# AK4558EN_PMOD.net
KiCad netlist of a schematic drawn in EAGLE
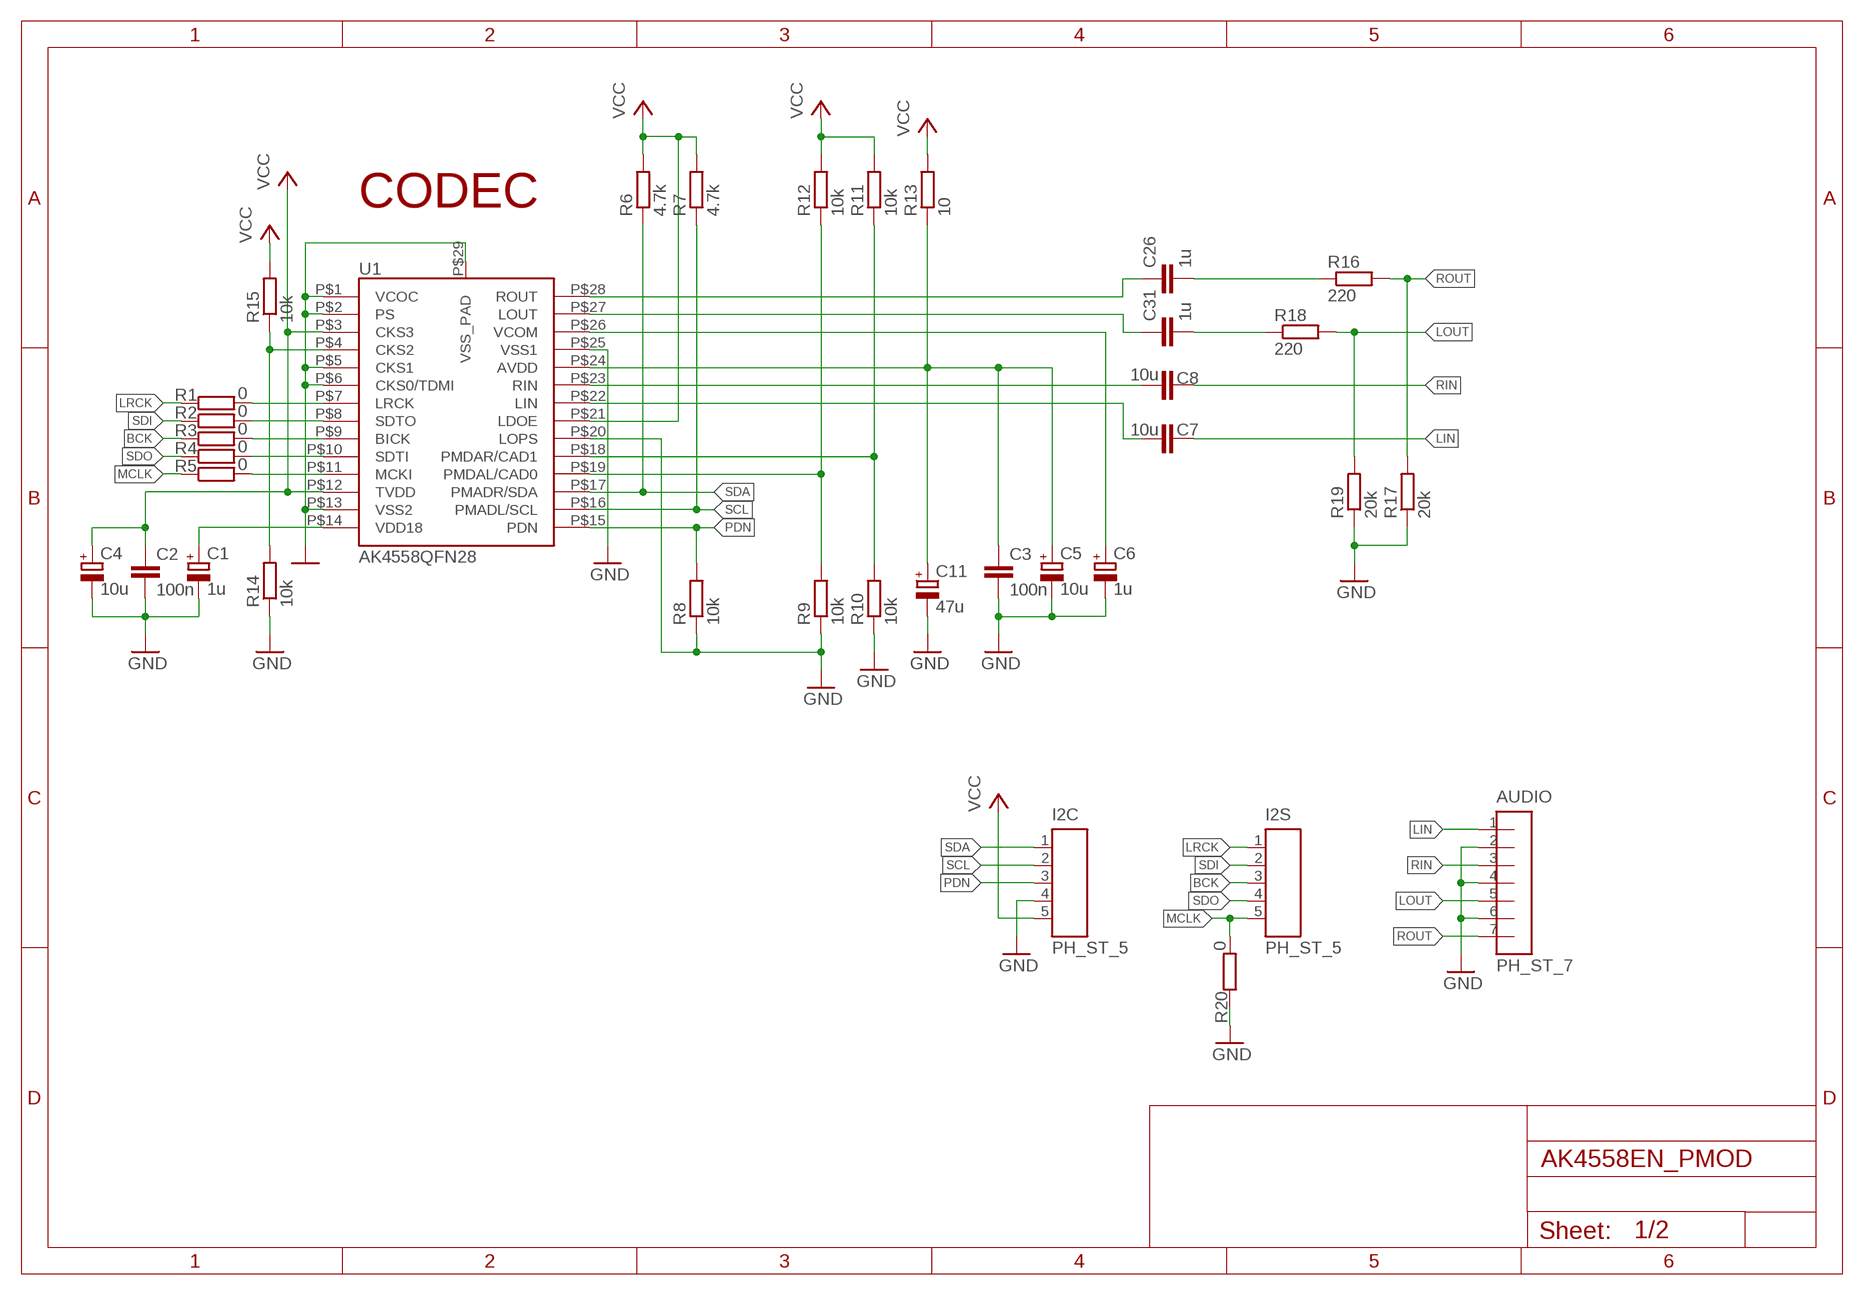
[diagram p0: schematic, sheet 1]
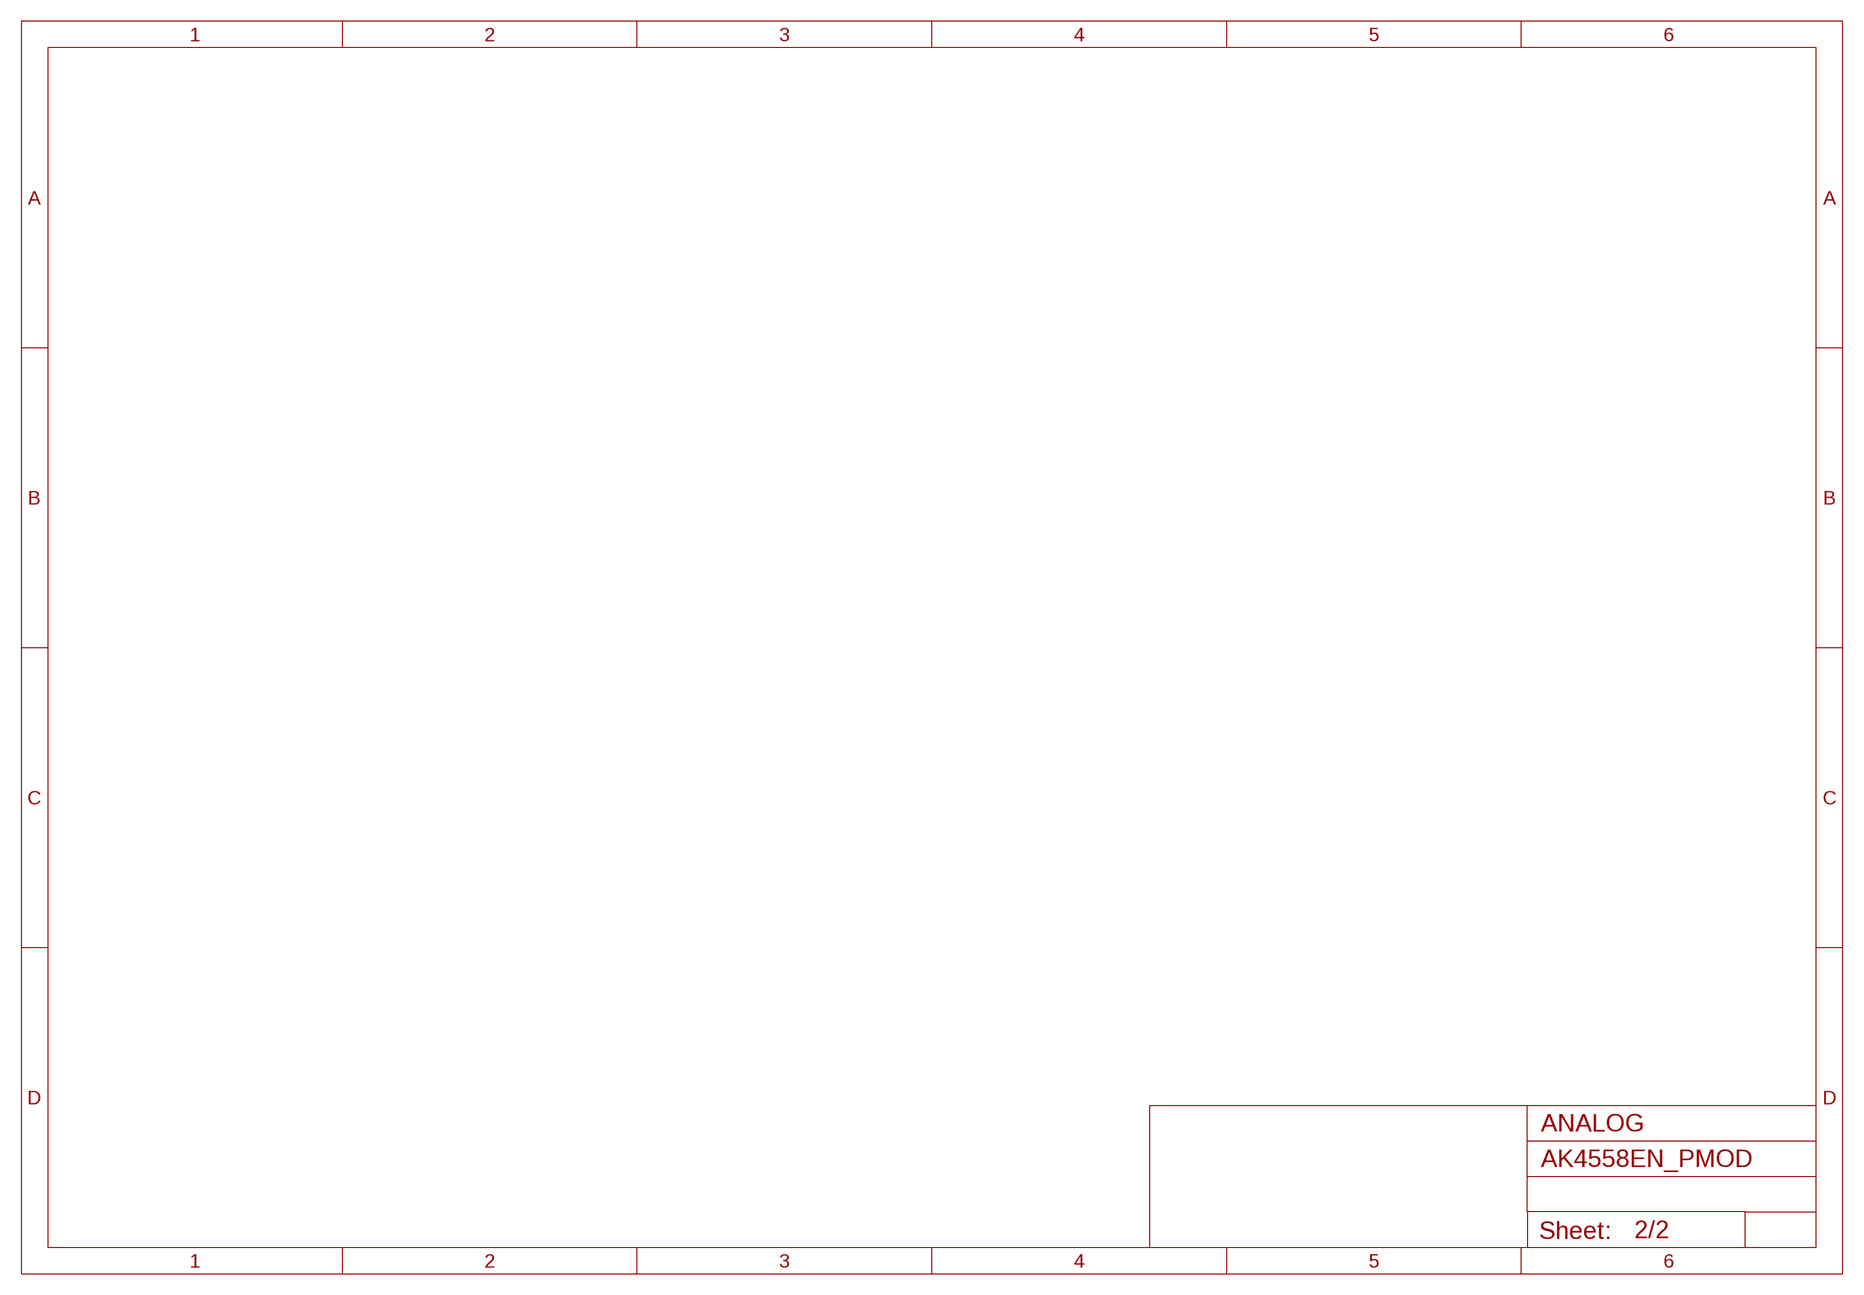
[diagram p1: schematic, sheet 2]

(export (version "E")
  (design (tool "Eeschema 10.0.6"))
  (components
    (comp (ref "AUDIO")
      (value "PH_ST_7")
      (footprint "eagle-import:HDRV7W64P254_1X7_1016X508X838B")
      (libsource (lib "eagle-import") (part "PH_ST_7"))
    )
    (comp (ref "C1")
      (value "1u")
      (footprint "eagle-import:SMC_A")
      (libsource (lib "eagle-import") (part "CPOL-EUSMCA"))
    )
    (comp (ref "C2")
      (value "100n")
      (footprint "eagle-import:C0603")
      (libsource (lib "eagle-import") (part "C-EUC0603"))
    )
    (comp (ref "C3")
      (value "100n")
      (footprint "eagle-import:C0603")
      (libsource (lib "eagle-import") (part "C-EUC0603"))
    )
    (comp (ref "C4")
      (value "10u")
      (footprint "eagle-import:SMC_B")
      (libsource (lib "eagle-import") (part "CPOL-EUSMCB"))
    )
    (comp (ref "C5")
      (value "10u")
      (footprint "eagle-import:SMC_B")
      (libsource (lib "eagle-import") (part "CPOL-EUSMCB"))
    )
    (comp (ref "C6")
      (value "1u")
      (footprint "eagle-import:SMC_A")
      (libsource (lib "eagle-import") (part "CPOL-EUSMCA"))
    )
    (comp (ref "C7")
      (value "10u")
      (footprint "eagle-import:C0603")
      (libsource (lib "eagle-import") (part "C-EUC0603"))
    )
    (comp (ref "C8")
      (value "10u")
      (footprint "eagle-import:C0603")
      (libsource (lib "eagle-import") (part "C-EUC0603"))
    )
    (comp (ref "C11")
      (value "47u")
      (footprint "eagle-import:SMC_C")
      (libsource (lib "eagle-import") (part "CPOL-EUSMCC"))
    )
    (comp (ref "C26")
      (value "1u")
      (footprint "eagle-import:C0603")
      (libsource (lib "eagle-import") (part "C-EUC0603"))
    )
    (comp (ref "C31")
      (value "1u")
      (footprint "eagle-import:C0603")
      (libsource (lib "eagle-import") (part "C-EUC0603"))
    )
    (comp (ref "I2C")
      (value "PH_ST_5")
      (footprint "eagle-import:HDRV5W64P254_1X5_1016X508X838B")
      (libsource (lib "eagle-import") (part "PH_ST_5"))
    )
    (comp (ref "I2S")
      (value "PH_ST_5")
      (footprint "eagle-import:HDRV5W64P254_1X5_1016X508X838B")
      (libsource (lib "eagle-import") (part "PH_ST_5"))
    )
    (comp (ref "R1")
      (value "0")
      (footprint "eagle-import:R0603")
      (libsource (lib "eagle-import") (part "R-EU_R0603"))
    )
    (comp (ref "R2")
      (value "0")
      (footprint "eagle-import:R0603")
      (libsource (lib "eagle-import") (part "R-EU_R0603"))
    )
    (comp (ref "R3")
      (value "0")
      (footprint "eagle-import:R0603")
      (libsource (lib "eagle-import") (part "R-EU_R0603"))
    )
    (comp (ref "R4")
      (value "0")
      (footprint "eagle-import:R0603")
      (libsource (lib "eagle-import") (part "R-EU_R0603"))
    )
    (comp (ref "R5")
      (value "0")
      (footprint "eagle-import:R0603")
      (libsource (lib "eagle-import") (part "R-EU_R0603"))
    )
    (comp (ref "R6")
      (value "4.7k")
      (footprint "eagle-import:R0603")
      (libsource (lib "eagle-import") (part "R-EU_R0603"))
    )
    (comp (ref "R7")
      (value "4.7k")
      (footprint "eagle-import:R0603")
      (libsource (lib "eagle-import") (part "R-EU_R0603"))
    )
    (comp (ref "R8")
      (value "10k")
      (footprint "eagle-import:R0603")
      (libsource (lib "eagle-import") (part "R-EU_R0603"))
    )
    (comp (ref "R9")
      (value "10k")
      (footprint "eagle-import:R0603")
      (libsource (lib "eagle-import") (part "R-EU_R0603"))
    )
    (comp (ref "R10")
      (value "10k")
      (footprint "eagle-import:R0603")
      (libsource (lib "eagle-import") (part "R-EU_R0603"))
    )
    (comp (ref "R11")
      (value "10k")
      (footprint "eagle-import:R0603")
      (libsource (lib "eagle-import") (part "R-EU_R0603"))
    )
    (comp (ref "R12")
      (value "10k")
      (footprint "eagle-import:R0603")
      (libsource (lib "eagle-import") (part "R-EU_R0603"))
    )
    (comp (ref "R13")
      (value "10")
      (footprint "eagle-import:R0603")
      (libsource (lib "eagle-import") (part "R-EU_R0603"))
    )
    (comp (ref "R14")
      (value "10k")
      (footprint "eagle-import:R0603")
      (libsource (lib "eagle-import") (part "R-EU_R0603"))
    )
    (comp (ref "R15")
      (value "10k")
      (footprint "eagle-import:R0603")
      (libsource (lib "eagle-import") (part "R-EU_R0603"))
    )
    (comp (ref "R16")
      (value "220")
      (footprint "eagle-import:R0603")
      (libsource (lib "eagle-import") (part "R-EU_R0603"))
    )
    (comp (ref "R17")
      (value "20k")
      (footprint "eagle-import:R0603")
      (libsource (lib "eagle-import") (part "R-EU_R0603"))
    )
    (comp (ref "R18")
      (value "220")
      (footprint "eagle-import:R0603")
      (libsource (lib "eagle-import") (part "R-EU_R0603"))
    )
    (comp (ref "R19")
      (value "20k")
      (footprint "eagle-import:R0603")
      (libsource (lib "eagle-import") (part "R-EU_R0603"))
    )
    (comp (ref "R20")
      (value "0")
      (footprint "eagle-import:R0603")
      (libsource (lib "eagle-import") (part "R-EU_R0603"))
    )
    (comp (ref "U1")
      (value "AK4558QFN28")
      (footprint "eagle-import:QFN28_5X5")
      (libsource (lib "eagle-import") (part "AK4558QFN28"))
    )
  )
  (nets
    (net (code "1") (name "BCK") (class "Default")
      (node (ref "I2S") (pin "3") (pinfunction "P$5_3") (pintype "bidirectional"))
      (node (ref "R3") (pin "1") (pinfunction "1_1") (pintype "passive"))
    )
    (net (code "2") (name "GND") (class "Default")
      (node (ref "AUDIO") (pin "2") (pinfunction "P$2_2") (pintype "bidirectional"))
      (node (ref "AUDIO") (pin "4") (pinfunction "P$4_4") (pintype "bidirectional"))
      (node (ref "AUDIO") (pin "6") (pinfunction "P$6_6") (pintype "bidirectional"))
      (node (ref "C1") (pin "-") (pinfunction "-_-") (pintype "passive"))
      (node (ref "C11") (pin "-") (pinfunction "-_-") (pintype "passive"))
      (node (ref "C2") (pin "2") (pinfunction "2_2") (pintype "passive"))
      (node (ref "C3") (pin "2") (pinfunction "2_2") (pintype "passive"))
      (node (ref "C4") (pin "-") (pinfunction "-_-") (pintype "passive"))
      (node (ref "C5") (pin "-") (pinfunction "-_-") (pintype "passive"))
      (node (ref "C6") (pin "-") (pinfunction "-_-") (pintype "passive"))
      (node (ref "I2C") (pin "4") (pinfunction "P$7_4") (pintype "bidirectional"))
      (node (ref "R10") (pin "1") (pinfunction "1_1") (pintype "passive"))
      (node (ref "R14") (pin "1") (pinfunction "1_1") (pintype "passive"))
      (node (ref "R17") (pin "1") (pinfunction "1_1") (pintype "passive"))
      (node (ref "R19") (pin "1") (pinfunction "1_1") (pintype "passive"))
      (node (ref "R20") (pin "1") (pinfunction "1_1") (pintype "passive"))
      (node (ref "R8") (pin "1") (pinfunction "1_1") (pintype "passive"))
      (node (ref "R9") (pin "1") (pinfunction "1_1") (pintype "passive"))
      (node (ref "U1") (pin "P$1") (pinfunction "VCOC_P$1") (pintype "bidirectional"))
      (node (ref "U1") (pin "P$13") (pinfunction "VSS2_P$13") (pintype "bidirectional"))
      (node (ref "U1") (pin "P$2") (pinfunction "PS_P$2") (pintype "bidirectional"))
      (node (ref "U1") (pin "P$20") (pinfunction "LOPS_P$20") (pintype "bidirectional"))
      (node (ref "U1") (pin "P$25") (pinfunction "VSS1_P$25") (pintype "bidirectional"))
      (node (ref "U1") (pin "P$29") (pinfunction "VSS_PAD_P$29") (pintype "bidirectional"))
      (node (ref "U1") (pin "P$5") (pinfunction "CKS1_P$5") (pintype "bidirectional"))
      (node (ref "U1") (pin "P$6") (pinfunction "CKS0/TDMI_P$6") (pintype "bidirectional"))
    )
    (net (code "3") (name "LIN") (class "Default")
      (node (ref "AUDIO") (pin "1") (pinfunction "P$1_1") (pintype "bidirectional"))
      (node (ref "C7") (pin "1") (pinfunction "1_1") (pintype "passive"))
    )
    (net (code "4") (name "LOUT") (class "Default")
      (node (ref "AUDIO") (pin "5") (pinfunction "P$5_5") (pintype "bidirectional"))
      (node (ref "R18") (pin "2") (pinfunction "2_2") (pintype "passive"))
      (node (ref "R19") (pin "2") (pinfunction "2_2") (pintype "passive"))
    )
    (net (code "5") (name "LRCK") (class "Default")
      (node (ref "I2S") (pin "1") (pinfunction "P$1_1") (pintype "bidirectional"))
      (node (ref "R1") (pin "1") (pinfunction "1_1") (pintype "passive"))
    )
    (net (code "6") (name "MCLK") (class "Default")
      (node (ref "I2S") (pin "5") (pinfunction "P$9_5") (pintype "bidirectional"))
      (node (ref "R20") (pin "2") (pinfunction "2_2") (pintype "passive"))
      (node (ref "R5") (pin "1") (pinfunction "1_1") (pintype "passive"))
    )
    (net (code "7") (name "Net-(C26-Pad2)") (class "Default")
      (node (ref "C26") (pin "2") (pinfunction "2_2") (pintype "passive"))
      (node (ref "R16") (pin "1") (pinfunction "1_1") (pintype "passive"))
    )
    (net (code "8") (name "Net-(C31-Pad2)") (class "Default")
      (node (ref "C31") (pin "2") (pinfunction "2_2") (pintype "passive"))
      (node (ref "R18") (pin "1") (pinfunction "1_1") (pintype "passive"))
    )
    (net (code "9") (name "Net-(U1-AVDD)") (class "Default")
      (node (ref "C11") (pin "+") (pinfunction "+_+") (pintype "passive"))
      (node (ref "C3") (pin "1") (pinfunction "1_1") (pintype "passive"))
      (node (ref "C5") (pin "+") (pinfunction "+_+") (pintype "passive"))
      (node (ref "R13") (pin "1") (pinfunction "1_1") (pintype "passive"))
      (node (ref "U1") (pin "P$24") (pinfunction "AVDD_P$24") (pintype "power_in"))
    )
    (net (code "10") (name "Net-(U1-BICK)") (class "Default")
      (node (ref "R3") (pin "2") (pinfunction "2_2") (pintype "passive"))
      (node (ref "U1") (pin "P$9") (pinfunction "BICK_P$9") (pintype "bidirectional"))
    )
    (net (code "11") (name "Net-(U1-CKS2)") (class "Default")
      (node (ref "R14") (pin "2") (pinfunction "2_2") (pintype "passive"))
      (node (ref "R15") (pin "1") (pinfunction "1_1") (pintype "passive"))
      (node (ref "U1") (pin "P$4") (pinfunction "CKS2_P$4") (pintype "bidirectional"))
    )
    (net (code "12") (name "Net-(U1-LIN)") (class "Default")
      (node (ref "C7") (pin "2") (pinfunction "2_2") (pintype "passive"))
      (node (ref "U1") (pin "P$22") (pinfunction "LIN_P$22") (pintype "input"))
    )
    (net (code "13") (name "Net-(U1-LOUT)") (class "Default")
      (node (ref "C31") (pin "1") (pinfunction "1_1") (pintype "passive"))
      (node (ref "U1") (pin "P$27") (pinfunction "LOUT_P$27") (pintype "bidirectional"))
    )
    (net (code "14") (name "Net-(U1-LRCK)") (class "Default")
      (node (ref "R1") (pin "2") (pinfunction "2_2") (pintype "passive"))
      (node (ref "U1") (pin "P$7") (pinfunction "LRCK_P$7") (pintype "bidirectional"))
    )
    (net (code "15") (name "Net-(U1-MCKI)") (class "Default")
      (node (ref "R5") (pin "2") (pinfunction "2_2") (pintype "passive"))
      (node (ref "U1") (pin "P$11") (pinfunction "MCKI_P$11") (pintype "bidirectional"))
    )
    (net (code "16") (name "Net-(U1-PMDAL{slash}CAD0)") (class "Default")
      (node (ref "R12") (pin "1") (pinfunction "1_1") (pintype "passive"))
      (node (ref "R9") (pin "2") (pinfunction "2_2") (pintype "passive"))
      (node (ref "U1") (pin "P$19") (pinfunction "PMDAL/CAD0_P$19") (pintype "bidirectional"))
    )
    (net (code "17") (name "Net-(U1-PMDAR{slash}CAD1)") (class "Default")
      (node (ref "R10") (pin "2") (pinfunction "2_2") (pintype "passive"))
      (node (ref "R11") (pin "1") (pinfunction "1_1") (pintype "passive"))
      (node (ref "U1") (pin "P$18") (pinfunction "PMDAR/CAD1_P$18") (pintype "bidirectional"))
    )
    (net (code "18") (name "Net-(U1-RIN)") (class "Default")
      (node (ref "C8") (pin "2") (pinfunction "2_2") (pintype "passive"))
      (node (ref "U1") (pin "P$23") (pinfunction "RIN_P$23") (pintype "input"))
    )
    (net (code "19") (name "Net-(U1-ROUT)") (class "Default")
      (node (ref "C26") (pin "1") (pinfunction "1_1") (pintype "passive"))
      (node (ref "U1") (pin "P$28") (pinfunction "ROUT_P$28") (pintype "bidirectional"))
    )
    (net (code "20") (name "Net-(U1-SDTI)") (class "Default")
      (node (ref "R4") (pin "2") (pinfunction "2_2") (pintype "passive"))
      (node (ref "U1") (pin "P$10") (pinfunction "SDTI_P$10") (pintype "bidirectional"))
    )
    (net (code "21") (name "Net-(U1-SDTO)") (class "Default")
      (node (ref "R2") (pin "2") (pinfunction "2_2") (pintype "passive"))
      (node (ref "U1") (pin "P$8") (pinfunction "SDTO_P$8") (pintype "bidirectional"))
    )
    (net (code "22") (name "Net-(U1-VCOM)") (class "Default")
      (node (ref "C6") (pin "+") (pinfunction "+_+") (pintype "passive"))
      (node (ref "U1") (pin "P$26") (pinfunction "VCOM_P$26") (pintype "bidirectional"))
    )
    (net (code "23") (name "Net-(U1-VDD18)") (class "Default")
      (node (ref "C1") (pin "+") (pinfunction "+_+") (pintype "passive"))
      (node (ref "U1") (pin "P$14") (pinfunction "VDD18_P$14") (pintype "bidirectional"))
    )
    (net (code "24") (name "PDN") (class "Default")
      (node (ref "I2C") (pin "3") (pinfunction "P$5_3") (pintype "bidirectional"))
      (node (ref "R8") (pin "2") (pinfunction "2_2") (pintype "passive"))
      (node (ref "U1") (pin "P$15") (pinfunction "PDN_P$15") (pintype "bidirectional"))
    )
    (net (code "25") (name "RIN") (class "Default")
      (node (ref "AUDIO") (pin "3") (pinfunction "P$3_3") (pintype "bidirectional"))
      (node (ref "C8") (pin "1") (pinfunction "1_1") (pintype "passive"))
    )
    (net (code "26") (name "ROUT") (class "Default")
      (node (ref "AUDIO") (pin "7") (pinfunction "P$7_7") (pintype "bidirectional"))
      (node (ref "R16") (pin "2") (pinfunction "2_2") (pintype "passive"))
      (node (ref "R17") (pin "2") (pinfunction "2_2") (pintype "passive"))
    )
    (net (code "27") (name "SCL") (class "Default")
      (node (ref "I2C") (pin "2") (pinfunction "P$3_2") (pintype "bidirectional"))
      (node (ref "R7") (pin "1") (pinfunction "1_1") (pintype "passive"))
      (node (ref "U1") (pin "P$16") (pinfunction "PMADL/SCL_P$16") (pintype "bidirectional"))
    )
    (net (code "28") (name "SDA") (class "Default")
      (node (ref "I2C") (pin "1") (pinfunction "P$1_1") (pintype "bidirectional"))
      (node (ref "R6") (pin "1") (pinfunction "1_1") (pintype "passive"))
      (node (ref "U1") (pin "P$17") (pinfunction "PMADR/SDA_P$17") (pintype "bidirectional"))
    )
    (net (code "29") (name "SDI") (class "Default")
      (node (ref "I2S") (pin "2") (pinfunction "P$3_2") (pintype "bidirectional"))
      (node (ref "R2") (pin "1") (pinfunction "1_1") (pintype "passive"))
    )
    (net (code "30") (name "SDO") (class "Default")
      (node (ref "I2S") (pin "4") (pinfunction "P$7_4") (pintype "bidirectional"))
      (node (ref "R4") (pin "1") (pinfunction "1_1") (pintype "passive"))
    )
    (net (code "31") (name "VCC") (class "Default")
      (node (ref "C2") (pin "1") (pinfunction "1_1") (pintype "passive"))
      (node (ref "C4") (pin "+") (pinfunction "+_+") (pintype "passive"))
      (node (ref "I2C") (pin "5") (pinfunction "P$9_5") (pintype "bidirectional"))
      (node (ref "R11") (pin "2") (pinfunction "2_2") (pintype "passive"))
      (node (ref "R12") (pin "2") (pinfunction "2_2") (pintype "passive"))
      (node (ref "R13") (pin "2") (pinfunction "2_2") (pintype "passive"))
      (node (ref "R15") (pin "2") (pinfunction "2_2") (pintype "passive"))
      (node (ref "R6") (pin "2") (pinfunction "2_2") (pintype "passive"))
      (node (ref "R7") (pin "2") (pinfunction "2_2") (pintype "passive"))
      (node (ref "U1") (pin "P$12") (pinfunction "TVDD_P$12") (pintype "bidirectional"))
      (node (ref "U1") (pin "P$21") (pinfunction "LDOE_P$21") (pintype "bidirectional"))
      (node (ref "U1") (pin "P$3") (pinfunction "CKS3_P$3") (pintype "bidirectional"))
    )
  )
)
